# 7_cpu_registers_b.net
KiCad netlist of a schematic drawn in EAGLE
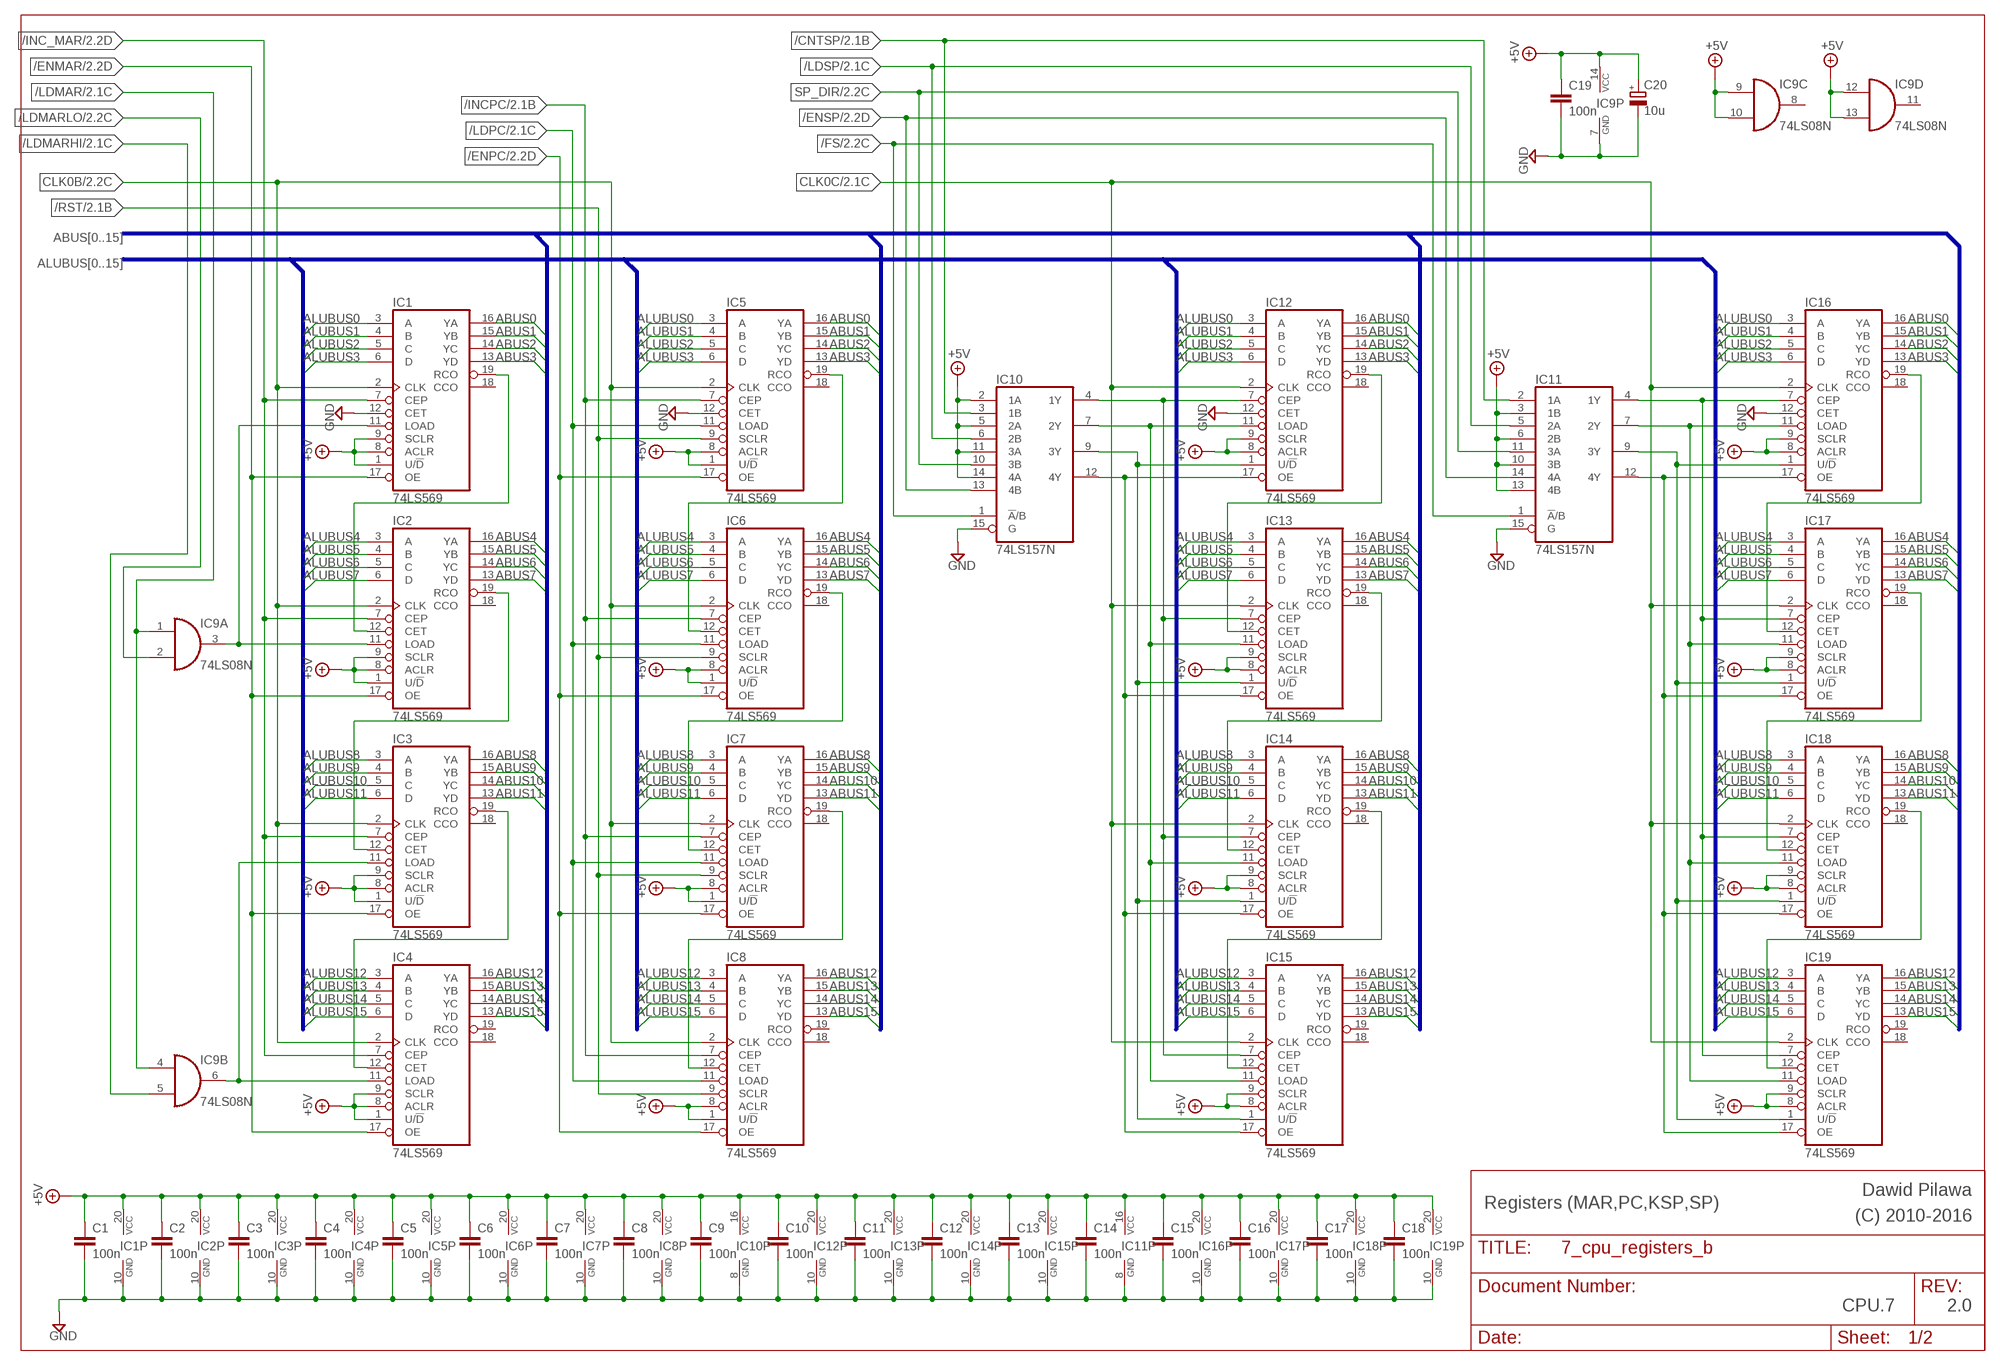
[diagram p0: schematic, sheet 1]
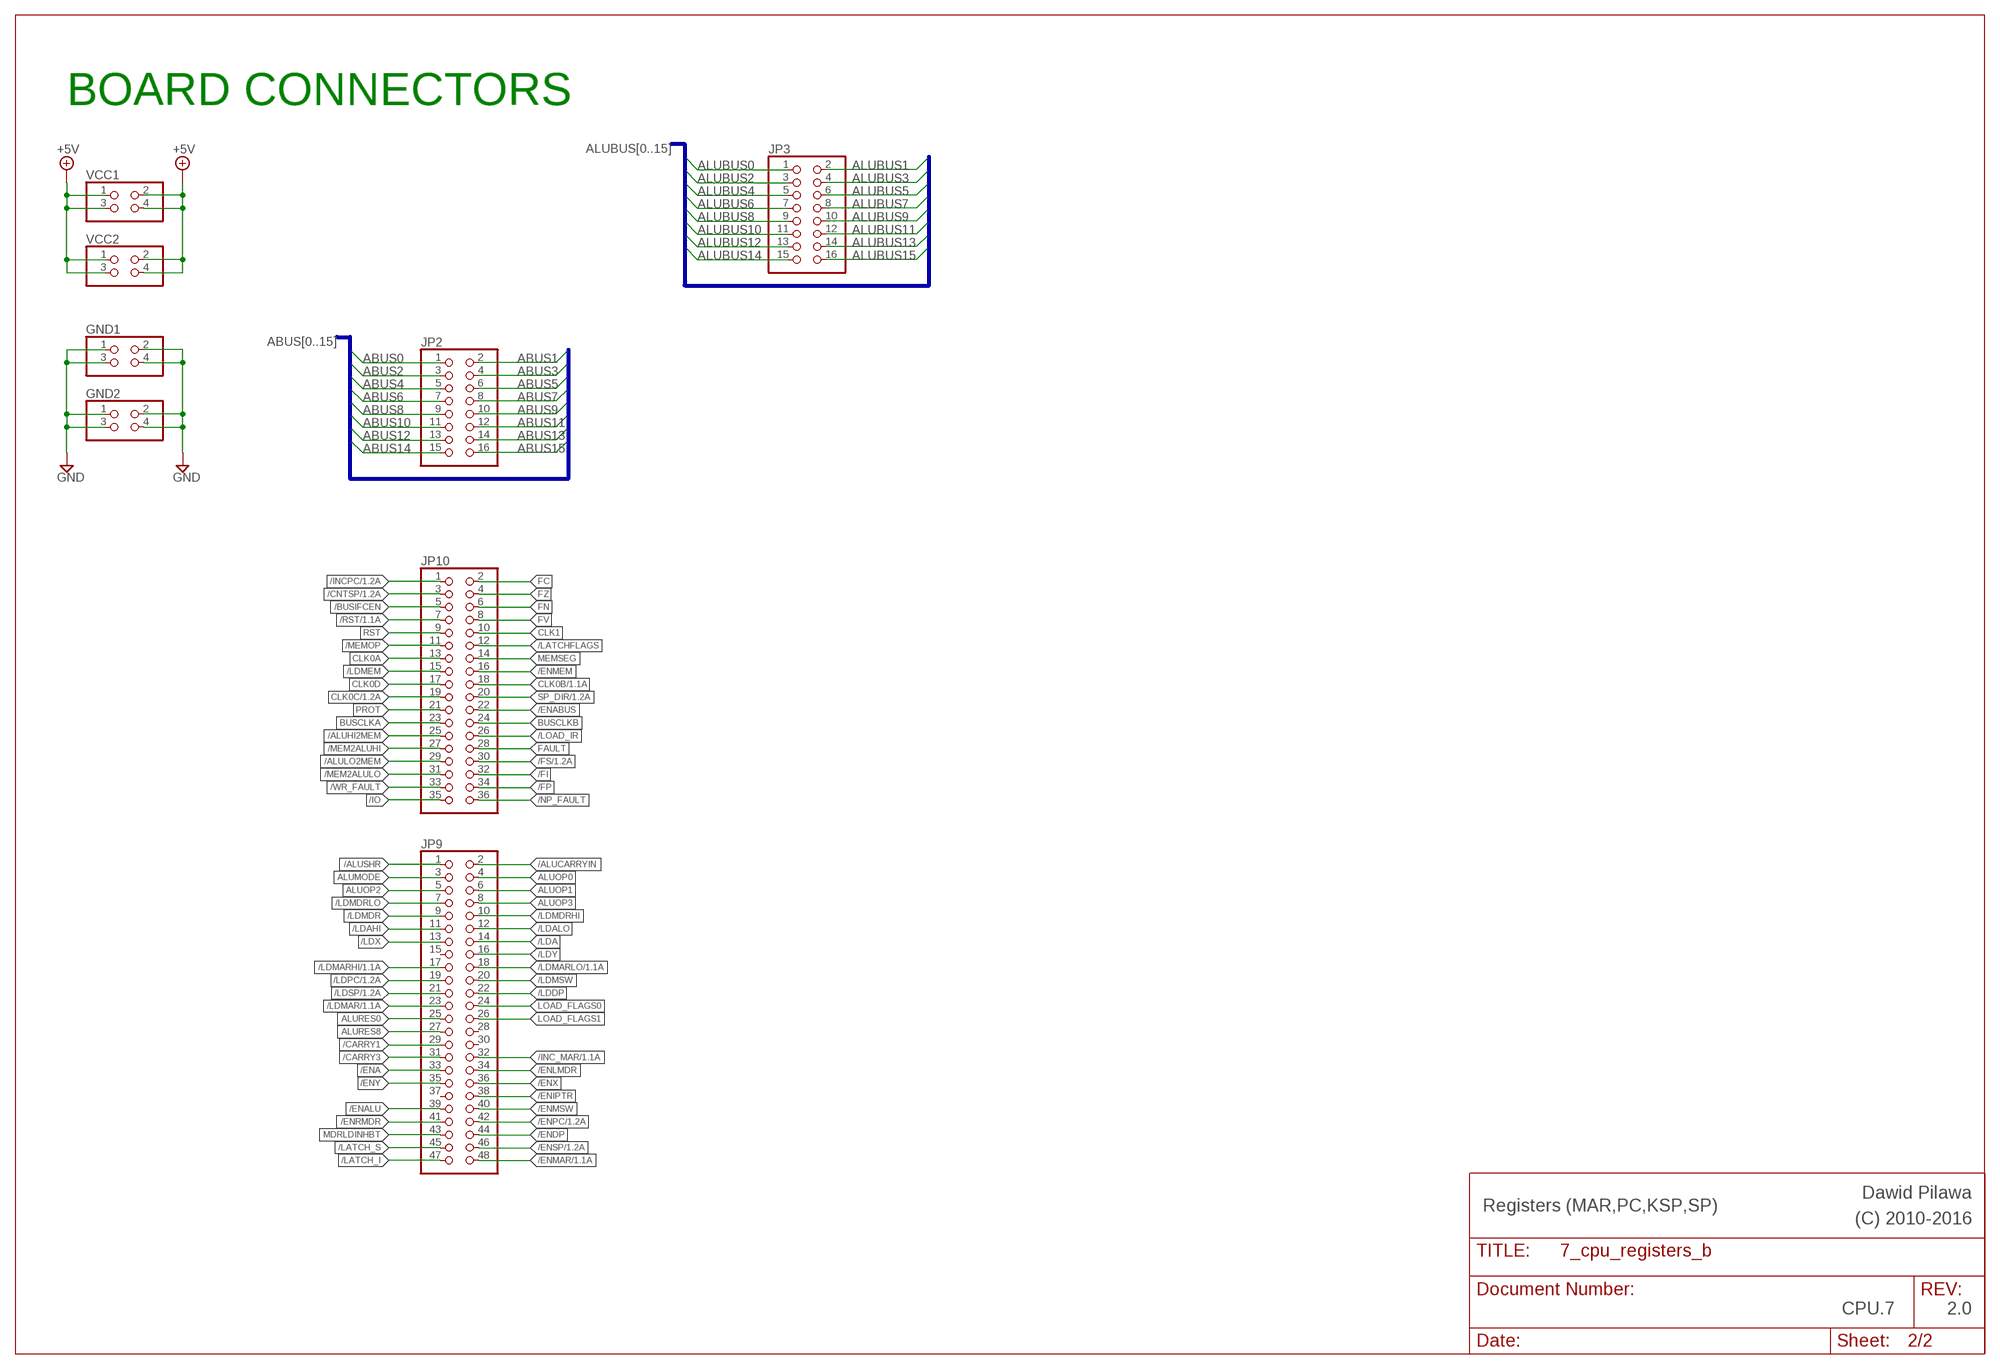
[diagram p1: schematic, sheet 2]

(export (version "E")
  (design (tool "Eeschema 10.0.6"))
  (components
    (comp (ref "C1")
      (value "100n")
      (footprint "eagle-import:C050-024X044")
      (libsource (lib "eagle-import") (part "C-EU050-024X044"))
    )
    (comp (ref "C2")
      (value "100n")
      (footprint "eagle-import:C050-024X044")
      (libsource (lib "eagle-import") (part "C-EU050-024X044"))
    )
    (comp (ref "C3")
      (value "100n")
      (footprint "eagle-import:C050-024X044")
      (libsource (lib "eagle-import") (part "C-EU050-024X044"))
    )
    (comp (ref "C4")
      (value "100n")
      (footprint "eagle-import:C050-024X044")
      (libsource (lib "eagle-import") (part "C-EU050-024X044"))
    )
    (comp (ref "C5")
      (value "100n")
      (footprint "eagle-import:C050-024X044")
      (libsource (lib "eagle-import") (part "C-EU050-024X044"))
    )
    (comp (ref "C6")
      (value "100n")
      (footprint "eagle-import:C050-024X044")
      (libsource (lib "eagle-import") (part "C-EU050-024X044"))
    )
    (comp (ref "C7")
      (value "100n")
      (footprint "eagle-import:C050-024X044")
      (libsource (lib "eagle-import") (part "C-EU050-024X044"))
    )
    (comp (ref "C8")
      (value "100n")
      (footprint "eagle-import:C050-024X044")
      (libsource (lib "eagle-import") (part "C-EU050-024X044"))
    )
    (comp (ref "C9")
      (value "100n")
      (footprint "eagle-import:C050-024X044")
      (libsource (lib "eagle-import") (part "C-EU050-024X044"))
    )
    (comp (ref "C10")
      (value "100n")
      (footprint "eagle-import:C050-024X044")
      (libsource (lib "eagle-import") (part "C-EU050-024X044"))
    )
    (comp (ref "C11")
      (value "100n")
      (footprint "eagle-import:C050-024X044")
      (libsource (lib "eagle-import") (part "C-EU050-024X044"))
    )
    (comp (ref "C12")
      (value "100n")
      (footprint "eagle-import:C050-024X044")
      (libsource (lib "eagle-import") (part "C-EU050-024X044"))
    )
    (comp (ref "C13")
      (value "100n")
      (footprint "eagle-import:C050-024X044")
      (libsource (lib "eagle-import") (part "C-EU050-024X044"))
    )
    (comp (ref "C14")
      (value "100n")
      (footprint "eagle-import:C050-024X044")
      (libsource (lib "eagle-import") (part "C-EU050-024X044"))
    )
    (comp (ref "C15")
      (value "100n")
      (footprint "eagle-import:C050-024X044")
      (libsource (lib "eagle-import") (part "C-EU050-024X044"))
    )
    (comp (ref "C16")
      (value "100n")
      (footprint "eagle-import:C050-024X044")
      (libsource (lib "eagle-import") (part "C-EU050-024X044"))
    )
    (comp (ref "C17")
      (value "100n")
      (footprint "eagle-import:C050-024X044")
      (libsource (lib "eagle-import") (part "C-EU050-024X044"))
    )
    (comp (ref "C18")
      (value "100n")
      (footprint "eagle-import:C050-024X044")
      (libsource (lib "eagle-import") (part "C-EU050-024X044"))
    )
    (comp (ref "C19")
      (value "100n")
      (footprint "eagle-import:C050-024X044")
      (libsource (lib "eagle-import") (part "C-EU050-024X044"))
    )
    (comp (ref "C20")
      (value "10u")
      (footprint "eagle-import:E2,5-6")
      (libsource (lib "eagle-import") (part "CPOL-EUE2.5-6"))
    )
    (comp (ref "IC1")
      (value "74LS569")
      (footprint "eagle-import:DIL20")
      (libsource (lib "eagle-import") (part "74569LS"))
    )
    (comp (ref "IC2")
      (value "74LS569")
      (footprint "eagle-import:DIL20")
      (libsource (lib "eagle-import") (part "74569LS"))
    )
    (comp (ref "IC3")
      (value "74LS569")
      (footprint "eagle-import:DIL20")
      (libsource (lib "eagle-import") (part "74569LS"))
    )
    (comp (ref "IC4")
      (value "74LS569")
      (footprint "eagle-import:DIL20")
      (libsource (lib "eagle-import") (part "74569LS"))
    )
    (comp (ref "IC5")
      (value "74LS569")
      (footprint "eagle-import:DIL20")
      (libsource (lib "eagle-import") (part "74569LS"))
    )
    (comp (ref "IC6")
      (value "74LS569")
      (footprint "eagle-import:DIL20")
      (libsource (lib "eagle-import") (part "74569LS"))
    )
    (comp (ref "IC7")
      (value "74LS569")
      (footprint "eagle-import:DIL20")
      (libsource (lib "eagle-import") (part "74569LS"))
    )
    (comp (ref "IC8")
      (value "74LS569")
      (footprint "eagle-import:DIL20")
      (libsource (lib "eagle-import") (part "74569LS"))
    )
    (comp (ref "IC9")
      (value "74LS08N")
      (footprint "eagle-import:DIL14")
      (libsource (lib "eagle-import") (part "7408NLS"))
    )
    (comp (ref "IC10")
      (value "74LS157N")
      (footprint "eagle-import:DIL16")
      (libsource (lib "eagle-import") (part "74157NLS"))
    )
    (comp (ref "IC11")
      (value "74LS157N")
      (footprint "eagle-import:DIL16")
      (libsource (lib "eagle-import") (part "74157NLS"))
    )
    (comp (ref "IC12")
      (value "74LS569")
      (footprint "eagle-import:DIL20")
      (libsource (lib "eagle-import") (part "74569LS"))
    )
    (comp (ref "IC13")
      (value "74LS569")
      (footprint "eagle-import:DIL20")
      (libsource (lib "eagle-import") (part "74569LS"))
    )
    (comp (ref "IC14")
      (value "74LS569")
      (footprint "eagle-import:DIL20")
      (libsource (lib "eagle-import") (part "74569LS"))
    )
    (comp (ref "IC15")
      (value "74LS569")
      (footprint "eagle-import:DIL20")
      (libsource (lib "eagle-import") (part "74569LS"))
    )
    (comp (ref "IC16")
      (value "74LS569")
      (footprint "eagle-import:DIL20")
      (libsource (lib "eagle-import") (part "74569LS"))
    )
    (comp (ref "IC17")
      (value "74LS569")
      (footprint "eagle-import:DIL20")
      (libsource (lib "eagle-import") (part "74569LS"))
    )
    (comp (ref "IC18")
      (value "74LS569")
      (footprint "eagle-import:DIL20")
      (libsource (lib "eagle-import") (part "74569LS"))
    )
    (comp (ref "IC19")
      (value "74LS569")
      (footprint "eagle-import:DIL20")
      (libsource (lib "eagle-import") (part "74569LS"))
    )
    (comp (ref "GND1")
      (value "PINHD-2X2")
      (footprint "eagle-import:2X02")
      (libsource (lib "eagle-import") (part "PINHD-2X2"))
    )
    (comp (ref "GND2")
      (value "PINHD-2X2")
      (footprint "eagle-import:2X02")
      (libsource (lib "eagle-import") (part "PINHD-2X2"))
    )
    (comp (ref "JP2")
      (value "PINHD-2X8")
      (footprint "eagle-import:2X08")
      (libsource (lib "eagle-import") (part "PINHD-2X8"))
    )
    (comp (ref "JP3")
      (value "PINHD-2X8")
      (footprint "eagle-import:2X08")
      (libsource (lib "eagle-import") (part "PINHD-2X8"))
    )
    (comp (ref "JP9")
      (value "PINHD-2X24")
      (footprint "eagle-import:2X24")
      (libsource (lib "eagle-import") (part "PINHD-2X24"))
    )
    (comp (ref "JP10")
      (value "PINHD-2X18")
      (footprint "eagle-import:2X18")
      (libsource (lib "eagle-import") (part "PINHD-2X18"))
    )
    (comp (ref "VCC1")
      (value "PINHD-2X2")
      (footprint "eagle-import:2X02")
      (libsource (lib "eagle-import") (part "PINHD-2X2"))
    )
    (comp (ref "VCC2")
      (value "PINHD-2X2")
      (footprint "eagle-import:2X02")
      (libsource (lib "eagle-import") (part "PINHD-2X2"))
    )
  )
  (nets
    (net (code "1") (name "+5V") (class "Default")
      (node (ref "C1") (pin "1") (pinfunction "1_1") (pintype "passive"))
      (node (ref "C10") (pin "1") (pinfunction "1_1") (pintype "passive"))
      (node (ref "C11") (pin "1") (pinfunction "1_1") (pintype "passive"))
      (node (ref "C12") (pin "1") (pinfunction "1_1") (pintype "passive"))
      (node (ref "C13") (pin "1") (pinfunction "1_1") (pintype "passive"))
      (node (ref "C14") (pin "1") (pinfunction "1_1") (pintype "passive"))
      (node (ref "C15") (pin "1") (pinfunction "1_1") (pintype "passive"))
      (node (ref "C16") (pin "1") (pinfunction "1_1") (pintype "passive"))
      (node (ref "C17") (pin "1") (pinfunction "1_1") (pintype "passive"))
      (node (ref "C18") (pin "1") (pinfunction "1_1") (pintype "passive"))
      (node (ref "C19") (pin "1") (pinfunction "1_1") (pintype "passive"))
      (node (ref "C2") (pin "1") (pinfunction "1_1") (pintype "passive"))
      (node (ref "C20") (pin "+") (pinfunction "+_+") (pintype "passive"))
      (node (ref "C3") (pin "1") (pinfunction "1_1") (pintype "passive"))
      (node (ref "C4") (pin "1") (pinfunction "1_1") (pintype "passive"))
      (node (ref "C5") (pin "1") (pinfunction "1_1") (pintype "passive"))
      (node (ref "C6") (pin "1") (pinfunction "1_1") (pintype "passive"))
      (node (ref "C7") (pin "1") (pinfunction "1_1") (pintype "passive"))
      (node (ref "C8") (pin "1") (pinfunction "1_1") (pintype "passive"))
      (node (ref "C9") (pin "1") (pinfunction "1_1") (pintype "passive"))
      (node (ref "IC1") (pin "1") (pinfunction "U/~{D}_1") (pintype "input"))
      (node (ref "IC1") (pin "20") (pinfunction "VCC_20") (pintype "power_in"))
      (node (ref "IC1") (pin "8") (pinfunction "ACLR_8") (pintype "input"))
      (node (ref "IC1") (pin "9") (pinfunction "SCLR_9") (pintype "input"))
      (node (ref "IC10") (pin "11") (pinfunction "3A_11") (pintype "input"))
      (node (ref "IC10") (pin "14") (pinfunction "4A_14") (pintype "input"))
      (node (ref "IC10") (pin "16") (pinfunction "VCC_16") (pintype "power_in"))
      (node (ref "IC10") (pin "2") (pinfunction "1A_2") (pintype "input"))
      (node (ref "IC10") (pin "5") (pinfunction "2A_5") (pintype "input"))
      (node (ref "IC11") (pin "10") (pinfunction "3B_10") (pintype "input"))
      (node (ref "IC11") (pin "13") (pinfunction "4B_13") (pintype "input"))
      (node (ref "IC11") (pin "16") (pinfunction "VCC_16") (pintype "power_in"))
      (node (ref "IC11") (pin "3") (pinfunction "1B_3") (pintype "input"))
      (node (ref "IC11") (pin "6") (pinfunction "2B_6") (pintype "input"))
      (node (ref "IC12") (pin "20") (pinfunction "VCC_20") (pintype "power_in"))
      (node (ref "IC12") (pin "8") (pinfunction "ACLR_8") (pintype "input"))
      (node (ref "IC12") (pin "9") (pinfunction "SCLR_9") (pintype "input"))
      (node (ref "IC13") (pin "20") (pinfunction "VCC_20") (pintype "power_in"))
      (node (ref "IC13") (pin "8") (pinfunction "ACLR_8") (pintype "input"))
      (node (ref "IC13") (pin "9") (pinfunction "SCLR_9") (pintype "input"))
      (node (ref "IC14") (pin "20") (pinfunction "VCC_20") (pintype "power_in"))
      (node (ref "IC14") (pin "8") (pinfunction "ACLR_8") (pintype "input"))
      (node (ref "IC14") (pin "9") (pinfunction "SCLR_9") (pintype "input"))
      (node (ref "IC15") (pin "20") (pinfunction "VCC_20") (pintype "power_in"))
      (node (ref "IC15") (pin "8") (pinfunction "ACLR_8") (pintype "input"))
      (node (ref "IC15") (pin "9") (pinfunction "SCLR_9") (pintype "input"))
      (node (ref "IC16") (pin "20") (pinfunction "VCC_20") (pintype "power_in"))
      (node (ref "IC16") (pin "8") (pinfunction "ACLR_8") (pintype "input"))
      (node (ref "IC16") (pin "9") (pinfunction "SCLR_9") (pintype "input"))
      (node (ref "IC17") (pin "20") (pinfunction "VCC_20") (pintype "power_in"))
      (node (ref "IC17") (pin "8") (pinfunction "ACLR_8") (pintype "input"))
      (node (ref "IC17") (pin "9") (pinfunction "SCLR_9") (pintype "input"))
      (node (ref "IC18") (pin "20") (pinfunction "VCC_20") (pintype "power_in"))
      (node (ref "IC18") (pin "8") (pinfunction "ACLR_8") (pintype "input"))
      (node (ref "IC18") (pin "9") (pinfunction "SCLR_9") (pintype "input"))
      (node (ref "IC19") (pin "20") (pinfunction "VCC_20") (pintype "power_in"))
      (node (ref "IC19") (pin "8") (pinfunction "ACLR_8") (pintype "input"))
      (node (ref "IC19") (pin "9") (pinfunction "SCLR_9") (pintype "input"))
      (node (ref "IC2") (pin "1") (pinfunction "U/~{D}_1") (pintype "input"))
      (node (ref "IC2") (pin "20") (pinfunction "VCC_20") (pintype "power_in"))
      (node (ref "IC2") (pin "8") (pinfunction "ACLR_8") (pintype "input"))
      (node (ref "IC2") (pin "9") (pinfunction "SCLR_9") (pintype "input"))
      (node (ref "IC3") (pin "1") (pinfunction "U/~{D}_1") (pintype "input"))
      (node (ref "IC3") (pin "20") (pinfunction "VCC_20") (pintype "power_in"))
      (node (ref "IC3") (pin "8") (pinfunction "ACLR_8") (pintype "input"))
      (node (ref "IC3") (pin "9") (pinfunction "SCLR_9") (pintype "input"))
      (node (ref "IC4") (pin "1") (pinfunction "U/~{D}_1") (pintype "input"))
      (node (ref "IC4") (pin "20") (pinfunction "VCC_20") (pintype "power_in"))
      (node (ref "IC4") (pin "8") (pinfunction "ACLR_8") (pintype "input"))
      (node (ref "IC4") (pin "9") (pinfunction "SCLR_9") (pintype "input"))
      (node (ref "IC5") (pin "1") (pinfunction "U/~{D}_1") (pintype "input"))
      (node (ref "IC5") (pin "20") (pinfunction "VCC_20") (pintype "power_in"))
      (node (ref "IC5") (pin "8") (pinfunction "ACLR_8") (pintype "input"))
      (node (ref "IC6") (pin "1") (pinfunction "U/~{D}_1") (pintype "input"))
      (node (ref "IC6") (pin "20") (pinfunction "VCC_20") (pintype "power_in"))
      (node (ref "IC6") (pin "8") (pinfunction "ACLR_8") (pintype "input"))
      (node (ref "IC7") (pin "1") (pinfunction "U/~{D}_1") (pintype "input"))
      (node (ref "IC7") (pin "20") (pinfunction "VCC_20") (pintype "power_in"))
      (node (ref "IC7") (pin "8") (pinfunction "ACLR_8") (pintype "input"))
      (node (ref "IC8") (pin "1") (pinfunction "U/~{D}_1") (pintype "input"))
      (node (ref "IC8") (pin "20") (pinfunction "VCC_20") (pintype "power_in"))
      (node (ref "IC8") (pin "8") (pinfunction "ACLR_8") (pintype "input"))
      (node (ref "IC9") (pin "10") (pinfunction "I1_10") (pintype "input"))
      (node (ref "IC9") (pin "12") (pinfunction "I0_12") (pintype "input"))
      (node (ref "IC9") (pin "13") (pinfunction "I1_13") (pintype "input"))
      (node (ref "IC9") (pin "14") (pinfunction "VCC_14") (pintype "power_in"))
      (node (ref "IC9") (pin "9") (pinfunction "I0_9") (pintype "input"))
      (node (ref "VCC1") (pin "1") (pinfunction "1_1") (pintype "passive"))
      (node (ref "VCC1") (pin "2") (pinfunction "2_2") (pintype "passive"))
      (node (ref "VCC1") (pin "3") (pinfunction "3_3") (pintype "passive"))
      (node (ref "VCC1") (pin "4") (pinfunction "4_4") (pintype "passive"))
      (node (ref "VCC2") (pin "1") (pinfunction "1_1") (pintype "passive"))
      (node (ref "VCC2") (pin "2") (pinfunction "2_2") (pintype "passive"))
      (node (ref "VCC2") (pin "3") (pinfunction "3_3") (pintype "passive"))
      (node (ref "VCC2") (pin "4") (pinfunction "4_4") (pintype "passive"))
    )
    (net (code "6") (name "ABUS0") (class "Default")
      (node (ref "IC1") (pin "16") (pinfunction "YA_16") (pintype "open_collector"))
      (node (ref "IC12") (pin "16") (pinfunction "YA_16") (pintype "open_collector"))
      (node (ref "IC16") (pin "16") (pinfunction "YA_16") (pintype "open_collector"))
      (node (ref "IC5") (pin "16") (pinfunction "YA_16") (pintype "open_collector"))
      (node (ref "JP2") (pin "1") (pinfunction "1_1") (pintype "passive"))
    )
    (net (code "7") (name "ABUS1") (class "Default")
      (node (ref "IC1") (pin "15") (pinfunction "YB_15") (pintype "open_collector"))
      (node (ref "IC12") (pin "15") (pinfunction "YB_15") (pintype "open_collector"))
      (node (ref "IC16") (pin "15") (pinfunction "YB_15") (pintype "open_collector"))
      (node (ref "IC5") (pin "15") (pinfunction "YB_15") (pintype "open_collector"))
      (node (ref "JP2") (pin "2") (pinfunction "2_2") (pintype "passive"))
    )
    (net (code "8") (name "ABUS2") (class "Default")
      (node (ref "IC1") (pin "14") (pinfunction "YC_14") (pintype "open_collector"))
      (node (ref "IC12") (pin "14") (pinfunction "YC_14") (pintype "open_collector"))
      (node (ref "IC16") (pin "14") (pinfunction "YC_14") (pintype "open_collector"))
      (node (ref "IC5") (pin "14") (pinfunction "YC_14") (pintype "open_collector"))
      (node (ref "JP2") (pin "3") (pinfunction "3_3") (pintype "passive"))
    )
    (net (code "9") (name "ABUS3") (class "Default")
      (node (ref "IC1") (pin "13") (pinfunction "YD_13") (pintype "open_collector"))
      (node (ref "IC12") (pin "13") (pinfunction "YD_13") (pintype "open_collector"))
      (node (ref "IC16") (pin "13") (pinfunction "YD_13") (pintype "open_collector"))
      (node (ref "IC5") (pin "13") (pinfunction "YD_13") (pintype "open_collector"))
      (node (ref "JP2") (pin "4") (pinfunction "4_4") (pintype "passive"))
    )
    (net (code "10") (name "ABUS4") (class "Default")
      (node (ref "IC13") (pin "16") (pinfunction "YA_16") (pintype "open_collector"))
      (node (ref "IC17") (pin "16") (pinfunction "YA_16") (pintype "open_collector"))
      (node (ref "IC2") (pin "16") (pinfunction "YA_16") (pintype "open_collector"))
      (node (ref "IC6") (pin "16") (pinfunction "YA_16") (pintype "open_collector"))
      (node (ref "JP2") (pin "5") (pinfunction "5_5") (pintype "passive"))
    )
    (net (code "11") (name "ABUS5") (class "Default")
      (node (ref "IC13") (pin "15") (pinfunction "YB_15") (pintype "open_collector"))
      (node (ref "IC17") (pin "15") (pinfunction "YB_15") (pintype "open_collector"))
      (node (ref "IC2") (pin "15") (pinfunction "YB_15") (pintype "open_collector"))
      (node (ref "IC6") (pin "15") (pinfunction "YB_15") (pintype "open_collector"))
      (node (ref "JP2") (pin "6") (pinfunction "6_6") (pintype "passive"))
    )
    (net (code "12") (name "ABUS6") (class "Default")
      (node (ref "IC13") (pin "14") (pinfunction "YC_14") (pintype "open_collector"))
      (node (ref "IC17") (pin "14") (pinfunction "YC_14") (pintype "open_collector"))
      (node (ref "IC2") (pin "14") (pinfunction "YC_14") (pintype "open_collector"))
      (node (ref "IC6") (pin "14") (pinfunction "YC_14") (pintype "open_collector"))
      (node (ref "JP2") (pin "7") (pinfunction "7_7") (pintype "passive"))
    )
    (net (code "13") (name "ABUS7") (class "Default")
      (node (ref "IC13") (pin "13") (pinfunction "YD_13") (pintype "open_collector"))
      (node (ref "IC17") (pin "13") (pinfunction "YD_13") (pintype "open_collector"))
      (node (ref "IC2") (pin "13") (pinfunction "YD_13") (pintype "open_collector"))
      (node (ref "IC6") (pin "13") (pinfunction "YD_13") (pintype "open_collector"))
      (node (ref "JP2") (pin "8") (pinfunction "8_8") (pintype "passive"))
    )
    (net (code "14") (name "ABUS8") (class "Default")
      (node (ref "IC14") (pin "16") (pinfunction "YA_16") (pintype "open_collector"))
      (node (ref "IC18") (pin "16") (pinfunction "YA_16") (pintype "open_collector"))
      (node (ref "IC3") (pin "16") (pinfunction "YA_16") (pintype "open_collector"))
      (node (ref "IC7") (pin "16") (pinfunction "YA_16") (pintype "open_collector"))
      (node (ref "JP2") (pin "9") (pinfunction "9_9") (pintype "passive"))
    )
    (net (code "15") (name "ABUS9") (class "Default")
      (node (ref "IC14") (pin "15") (pinfunction "YB_15") (pintype "open_collector"))
      (node (ref "IC18") (pin "15") (pinfunction "YB_15") (pintype "open_collector"))
      (node (ref "IC3") (pin "15") (pinfunction "YB_15") (pintype "open_collector"))
      (node (ref "IC7") (pin "15") (pinfunction "YB_15") (pintype "open_collector"))
      (node (ref "JP2") (pin "10") (pinfunction "10_10") (pintype "passive"))
    )
    (net (code "16") (name "ABUS10") (class "Default")
      (node (ref "IC14") (pin "14") (pinfunction "YC_14") (pintype "open_collector"))
      (node (ref "IC18") (pin "14") (pinfunction "YC_14") (pintype "open_collector"))
      (node (ref "IC3") (pin "14") (pinfunction "YC_14") (pintype "open_collector"))
      (node (ref "IC7") (pin "14") (pinfunction "YC_14") (pintype "open_collector"))
      (node (ref "JP2") (pin "11") (pinfunction "11_11") (pintype "passive"))
    )
    (net (code "17") (name "ABUS11") (class "Default")
      (node (ref "IC14") (pin "13") (pinfunction "YD_13") (pintype "open_collector"))
      (node (ref "IC18") (pin "13") (pinfunction "YD_13") (pintype "open_collector"))
      (node (ref "IC3") (pin "13") (pinfunction "YD_13") (pintype "open_collector"))
      (node (ref "IC7") (pin "13") (pinfunction "YD_13") (pintype "open_collector"))
      (node (ref "JP2") (pin "12") (pinfunction "12_12") (pintype "passive"))
    )
    (net (code "18") (name "ABUS12") (class "Default")
      (node (ref "IC15") (pin "16") (pinfunction "YA_16") (pintype "open_collector"))
      (node (ref "IC19") (pin "16") (pinfunction "YA_16") (pintype "open_collector"))
      (node (ref "IC4") (pin "16") (pinfunction "YA_16") (pintype "open_collector"))
      (node (ref "IC8") (pin "16") (pinfunction "YA_16") (pintype "open_collector"))
      (node (ref "JP2") (pin "13") (pinfunction "13_13") (pintype "passive"))
    )
    (net (code "19") (name "ABUS13") (class "Default")
      (node (ref "IC15") (pin "15") (pinfunction "YB_15") (pintype "open_collector"))
      (node (ref "IC19") (pin "15") (pinfunction "YB_15") (pintype "open_collector"))
      (node (ref "IC4") (pin "15") (pinfunction "YB_15") (pintype "open_collector"))
      (node (ref "IC8") (pin "15") (pinfunction "YB_15") (pintype "open_collector"))
      (node (ref "JP2") (pin "14") (pinfunction "14_14") (pintype "passive"))
    )
    (net (code "20") (name "ABUS14") (class "Default")
      (node (ref "IC15") (pin "14") (pinfunction "YC_14") (pintype "open_collector"))
      (node (ref "IC19") (pin "14") (pinfunction "YC_14") (pintype "open_collector"))
      (node (ref "IC4") (pin "14") (pinfunction "YC_14") (pintype "open_collector"))
      (node (ref "IC8") (pin "14") (pinfunction "YC_14") (pintype "open_collector"))
      (node (ref "JP2") (pin "15") (pinfunction "15_15") (pintype "passive"))
    )
    (net (code "21") (name "ABUS15") (class "Default")
      (node (ref "IC15") (pin "13") (pinfunction "YD_13") (pintype "open_collector"))
      (node (ref "IC19") (pin "13") (pinfunction "YD_13") (pintype "open_collector"))
      (node (ref "IC4") (pin "13") (pinfunction "YD_13") (pintype "open_collector"))
      (node (ref "IC8") (pin "13") (pinfunction "YD_13") (pintype "open_collector"))
      (node (ref "JP2") (pin "16") (pinfunction "16_16") (pintype "passive"))
    )
    (net (code "22") (name "ALUBUS0") (class "Default")
      (node (ref "IC1") (pin "3") (pinfunction "A_3") (pintype "input"))
      (node (ref "IC12") (pin "3") (pinfunction "A_3") (pintype "input"))
      (node (ref "IC16") (pin "3") (pinfunction "A_3") (pintype "input"))
      (node (ref "IC5") (pin "3") (pinfunction "A_3") (pintype "input"))
      (node (ref "JP3") (pin "1") (pinfunction "1_1") (pintype "passive"))
    )
    (net (code "23") (name "ALUBUS1") (class "Default")
      (node (ref "IC1") (pin "4") (pinfunction "B_4") (pintype "input"))
      (node (ref "IC12") (pin "4") (pinfunction "B_4") (pintype "input"))
      (node (ref "IC16") (pin "4") (pinfunction "B_4") (pintype "input"))
      (node (ref "IC5") (pin "4") (pinfunction "B_4") (pintype "input"))
      (node (ref "JP3") (pin "2") (pinfunction "2_2") (pintype "passive"))
    )
    (net (code "24") (name "ALUBUS2") (class "Default")
      (node (ref "IC1") (pin "5") (pinfunction "C_5") (pintype "input"))
      (node (ref "IC12") (pin "5") (pinfunction "C_5") (pintype "input"))
      (node (ref "IC16") (pin "5") (pinfunction "C_5") (pintype "input"))
      (node (ref "IC5") (pin "5") (pinfunction "C_5") (pintype "input"))
      (node (ref "JP3") (pin "3") (pinfunction "3_3") (pintype "passive"))
    )
    (net (code "25") (name "ALUBUS3") (class "Default")
      (node (ref "IC1") (pin "6") (pinfunction "D_6") (pintype "input"))
      (node (ref "IC12") (pin "6") (pinfunction "D_6") (pintype "input"))
      (node (ref "IC16") (pin "6") (pinfunction "D_6") (pintype "input"))
      (node (ref "IC5") (pin "6") (pinfunction "D_6") (pintype "input"))
      (node (ref "JP3") (pin "4") (pinfunction "4_4") (pintype "passive"))
    )
    (net (code "26") (name "ALUBUS4") (class "Default")
      (node (ref "IC13") (pin "3") (pinfunction "A_3") (pintype "input"))
      (node (ref "IC17") (pin "3") (pinfunction "A_3") (pintype "input"))
      (node (ref "IC2") (pin "3") (pinfunction "A_3") (pintype "input"))
      (node (ref "IC6") (pin "3") (pinfunction "A_3") (pintype "input"))
      (node (ref "JP3") (pin "5") (pinfunction "5_5") (pintype "passive"))
    )
    (net (code "27") (name "ALUBUS5") (class "Default")
      (node (ref "IC13") (pin "4") (pinfunction "B_4") (pintype "input"))
      (node (ref "IC17") (pin "4") (pinfunction "B_4") (pintype "input"))
      (node (ref "IC2") (pin "4") (pinfunction "B_4") (pintype "input"))
      (node (ref "IC6") (pin "4") (pinfunction "B_4") (pintype "input"))
      (node (ref "JP3") (pin "6") (pinfunction "6_6") (pintype "passive"))
    )
    (net (code "28") (name "ALUBUS6") (class "Default")
      (node (ref "IC13") (pin "5") (pinfunction "C_5") (pintype "input"))
      (node (ref "IC17") (pin "5") (pinfunction "C_5") (pintype "input"))
      (node (ref "IC2") (pin "5") (pinfunction "C_5") (pintype "input"))
      (node (ref "IC6") (pin "5") (pinfunction "C_5") (pintype "input"))
      (node (ref "JP3") (pin "7") (pinfunction "7_7") (pintype "passive"))
    )
    (net (code "29") (name "ALUBUS7") (class "Default")
      (node (ref "IC13") (pin "6") (pinfunction "D_6") (pintype "input"))
      (node (ref "IC17") (pin "6") (pinfunction "D_6") (pintype "input"))
      (node (ref "IC2") (pin "6") (pinfunction "D_6") (pintype "input"))
      (node (ref "IC6") (pin "6") (pinfunction "D_6") (pintype "input"))
      (node (ref "JP3") (pin "8") (pinfunction "8_8") (pintype "passive"))
    )
    (net (code "30") (name "ALUBUS8") (class "Default")
      (node (ref "IC14") (pin "3") (pinfunction "A_3") (pintype "input"))
      (node (ref "IC18") (pin "3") (pinfunction "A_3") (pintype "input"))
      (node (ref "IC3") (pin "3") (pinfunction "A_3") (pintype "input"))
      (node (ref "IC7") (pin "3") (pinfunction "A_3") (pintype "input"))
      (node (ref "JP3") (pin "9") (pinfunction "9_9") (pintype "passive"))
    )
    (net (code "31") (name "ALUBUS9") (class "Default")
      (node (ref "IC14") (pin "4") (pinfunction "B_4") (pintype "input"))
      (node (ref "IC18") (pin "4") (pinfunction "B_4") (pintype "input"))
      (node (ref "IC3") (pin "4") (pinfunction "B_4") (pintype "input"))
      (node (ref "IC7") (pin "4") (pinfunction "B_4") (pintype "input"))
      (node (ref "JP3") (pin "10") (pinfunction "10_10") (pintype "passive"))
    )
    (net (code "32") (name "ALUBUS10") (class "Default")
      (node (ref "IC14") (pin "5") (pinfunction "C_5") (pintype "input"))
      (node (ref "IC18") (pin "5") (pinfunction "C_5") (pintype "input"))
      (node (ref "IC3") (pin "5") (pinfunction "C_5") (pintype "input"))
      (node (ref "IC7") (pin "5") (pinfunction "C_5") (pintype "input"))
      (node (ref "JP3") (pin "11") (pinfunction "11_11") (pintype "passive"))
    )
    (net (code "33") (name "ALUBUS11") (class "Default")
      (node (ref "IC14") (pin "6") (pinfunction "D_6") (pintype "input"))
      (node (ref "IC18") (pin "6") (pinfunction "D_6") (pintype "input"))
      (node (ref "IC3") (pin "6") (pinfunction "D_6") (pintype "input"))
      (node (ref "IC7") (pin "6") (pinfunction "D_6") (pintype "input"))
      (node (ref "JP3") (pin "12") (pinfunction "12_12") (pintype "passive"))
    )
    (net (code "34") (name "ALUBUS12") (class "Default")
      (node (ref "IC15") (pin "3") (pinfunction "A_3") (pintype "input"))
      (node (ref "IC19") (pin "3") (pinfunction "A_3") (pintype "input"))
      (node (ref "IC4") (pin "3") (pinfunction "A_3") (pintype "input"))
      (node (ref "IC8") (pin "3") (pinfunction "A_3") (pintype "input"))
      (node (ref "JP3") (pin "13") (pinfunction "13_13") (pintype "passive"))
    )
    (net (code "35") (name "ALUBUS13") (class "Default")
      (node (ref "IC15") (pin "4") (pinfunction "B_4") (pintype "input"))
      (node (ref "IC19") (pin "4") (pinfunction "B_4") (pintype "input"))
      (node (ref "IC4") (pin "4") (pinfunction "B_4") (pintype "input"))
      (node (ref "IC8") (pin "4") (pinfunction "B_4") (pintype "input"))
      (node (ref "JP3") (pin "14") (pinfunction "14_14") (pintype "passive"))
    )
    (net (code "36") (name "ALUBUS14") (class "Default")
      (node (ref "IC15") (pin "5") (pinfunction "C_5") (pintype "input"))
      (node (ref "IC19") (pin "5") (pinfunction "C_5") (pintype "input"))
      (node (ref "IC4") (pin "5") (pinfunction "C_5") (pintype "input"))
      (node (ref "IC8") (pin "5") (pinfunction "C_5") (pintype "input"))
      (node (ref "JP3") (pin "15") (pinfunction "15_15") (pintype "passive"))
    )
    (net (code "37") (name "ALUBUS15") (class "Default")
      (node (ref "IC15") (pin "6") (pinfunction "D_6") (pintype "input"))
      (node (ref "IC19") (pin "6") (pinfunction "D_6") (pintype "input"))
      (node (ref "IC4") (pin "6") (pinfunction "D_6") (pintype "input"))
      (node (ref "IC8") (pin "6") (pinfunction "D_6") (pintype "input"))
      (node (ref "JP3") (pin "16") (pinfunction "16_16") (pintype "passive"))
    )
    (net (code "38") (name "ALUMODE") (class "Default")
      (node (ref "JP9") (pin "3") (pinfunction "3_3") (pintype "passive"))
    )
    (net (code "39") (name "ALUOP0") (class "Default")
      (node (ref "JP9") (pin "4") (pinfunction "4_4") (pintype "passive"))
    )
    (net (code "40") (name "ALUOP1") (class "Default")
      (node (ref "JP9") (pin "6") (pinfunction "6_6") (pintype "passive"))
    )
    (net (code "41") (name "ALUOP2") (class "Default")
      (node (ref "JP9") (pin "5") (pinfunction "5_5") (pintype "passive"))
    )
    (net (code "42") (name "ALUOP3") (class "Default")
      (node (ref "JP9") (pin "8") (pinfunction "8_8") (pintype "passive"))
    )
    (net (code "43") (name "ALURES0") (class "Default")
      (node (ref "JP9") (pin "25") (pinfunction "25_25") (pintype "passive"))
    )
    (net (code "44") (name "ALURES8") (class "Default")
      (node (ref "JP9") (pin "27") (pinfunction "27_27") (pintype "passive"))
    )
    (net (code "45") (name "BUSCLKA") (class "Default")
      (node (ref "JP10") (pin "23") (pinfunction "23_23") (pintype "passive"))
    )
    (net (code "46") (name "BUSCLKB") (class "Default")
      (node (ref "JP10") (pin "24") (pinfunction "24_24") (pintype "passive"))
    )
    (net (code "47") (name "CLK0A") (class "Default")
      (node (ref "JP10") (pin "13") (pinfunction "13_13") (pintype "passive"))
    )
    (net (code "48") (name "CLK0B") (class "Default")
      (node (ref "IC1") (pin "2") (pinfunction "CLK_2") (pintype "input"))
      (node (ref "IC2") (pin "2") (pinfunction "CLK_2") (pintype "input"))
      (node (ref "IC3") (pin "2") (pinfunction "CLK_2") (pintype "input"))
      (node (ref "IC4") (pin "2") (pinfunction "CLK_2") (pintype "input"))
      (node (ref "IC5") (pin "2") (pinfunction "CLK_2") (pintype "input"))
      (node (ref "IC6") (pin "2") (pinfunction "CLK_2") (pintype "input"))
      (node (ref "IC7") (pin "2") (pinfunction "CLK_2") (pintype "input"))
      (node (ref "IC8") (pin "2") (pinfunction "CLK_2") (pintype "input"))
      (node (ref "JP10") (pin "18") (pinfunction "18_18") (pintype "passive"))
    )
    (net (code "49") (name "CLK0C") (class "Default")
      (node (ref "IC12") (pin "2") (pinfunction "CLK_2") (pintype "input"))
      (node (ref "IC13") (pin "2") (pinfunction "CLK_2") (pintype "input"))
      (node (ref "IC14") (pin "2") (pinfunction "CLK_2") (pintype "input"))
      (node (ref "IC15") (pin "2") (pinfunction "CLK_2") (pintype "input"))
      (node (ref "IC16") (pin "2") (pinfunction "CLK_2") (pintype "input"))
      (node (ref "IC17") (pin "2") (pinfunction "CLK_2") (pintype "input"))
      (node (ref "IC18") (pin "2") (pinfunction "CLK_2") (pintype "input"))
      (node (ref "IC19") (pin "2") (pinfunction "CLK_2") (pintype "input"))
      (node (ref "JP10") (pin "19") (pinfunction "19_19") (pintype "passive"))
    )
    (net (code "50") (name "CLK0D") (class "Default")
      (node (ref "JP10") (pin "17") (pinfunction "17_17") (pintype "passive"))
    )
    (net (code "51") (name "CLK1") (class "Default")
      (node (ref "JP10") (pin "10") (pinfunction "10_10") (pintype "passive"))
    )
    (net (code "52") (name "FAULT") (class "Default")
      (node (ref "JP10") (pin "28") (pinfunction "28_28") (pintype "passive"))
    )
    (net (code "53") (name "FC") (class "Default")
      (node (ref "JP10") (pin "2") (pinfunction "2_2") (pintype "passive"))
    )
    (net (code "54") (name "FN") (class "Default")
      (node (ref "JP10") (pin "6") (pinfunction "6_6") (pintype "passive"))
    )
    (net (code "55") (name "FV") (class "Default")
      (node (ref "JP10") (pin "8") (pinfunction "8_8") (pintype "passive"))
    )
    (net (code "56") (name "FZ") (class "Default")
      (node (ref "JP10") (pin "4") (pinfunction "4_4") (pintype "passive"))
    )
    (net (code "57") (name "GND") (class "Default")
      (node (ref "C1") (pin "2") (pinfunction "2_2") (pintype "passive"))
      (node (ref "C10") (pin "2") (pinfunction "2_2") (pintype "passive"))
      (node (ref "C11") (pin "2") (pinfunction "2_2") (pintype "passive"))
      (node (ref "C12") (pin "2") (pinfunction "2_2") (pintype "passive"))
      (node (ref "C13") (pin "2") (pinfunction "2_2") (pintype "passive"))
      (node (ref "C14") (pin "2") (pinfunction "2_2") (pintype "passive"))
      (node (ref "C15") (pin "2") (pinfunction "2_2") (pintype "passive"))
      (node (ref "C16") (pin "2") (pinfunction "2_2") (pintype "passive"))
      (node (ref "C17") (pin "2") (pinfunction "2_2") (pintype "passive"))
      (node (ref "C18") (pin "2") (pinfunction "2_2") (pintype "passive"))
      (node (ref "C19") (pin "2") (pinfunction "2_2") (pintype "passive"))
      (node (ref "C2") (pin "2") (pinfunction "2_2") (pintype "passive"))
      (node (ref "C20") (pin "-") (pinfunction "-_-") (pintype "passive"))
      (node (ref "C3") (pin "2") (pinfunction "2_2") (pintype "passive"))
      (node (ref "C4") (pin "2") (pinfunction "2_2") (pintype "passive"))
      (node (ref "C5") (pin "2") (pinfunction "2_2") (pintype "passive"))
      (node (ref "C6") (pin "2") (pinfunction "2_2") (pintype "passive"))
      (node (ref "C7") (pin "2") (pinfunction "2_2") (pintype "passive"))
      (node (ref "C8") (pin "2") (pinfunction "2_2") (pintype "passive"))
      (node (ref "C9") (pin "2") (pinfunction "2_2") (pintype "passive"))
      (node (ref "GND1") (pin "1") (pinfunction "1_1") (pintype "passive"))
      (node (ref "GND1") (pin "2") (pinfunction "2_2") (pintype "passive"))
      (node (ref "GND1") (pin "3") (pinfunction "3_3") (pintype "passive"))
      (node (ref "GND1") (pin "4") (pinfunction "4_4") (pintype "passive"))
      (node (ref "GND2") (pin "1") (pinfunction "1_1") (pintype "passive"))
      (node (ref "GND2") (pin "2") (pinfunction "2_2") (pintype "passive"))
      (node (ref "GND2") (pin "3") (pinfunction "3_3") (pintype "passive"))
      (node (ref "GND2") (pin "4") (pinfunction "4_4") (pintype "passive"))
      (node (ref "IC1") (pin "10") (pinfunction "GND_10") (pintype "power_in"))
      (node (ref "IC1") (pin "12") (pinfunction "CET_12") (pintype "input"))
      (node (ref "IC10") (pin "15") (pinfunction "G_15") (pintype "input"))
      (node (ref "IC10") (pin "8") (pinfunction "GND_8") (pintype "power_in"))
      (node (ref "IC11") (pin "15") (pinfunction "G_15") (pintype "input"))
      (node (ref "IC11") (pin "8") (pinfunction "GND_8") (pintype "power_in"))
      (node (ref "IC12") (pin "10") (pinfunction "GND_10") (pintype "power_in"))
      (node (ref "IC12") (pin "12") (pinfunction "CET_12") (pintype "input"))
      (node (ref "IC13") (pin "10") (pinfunction "GND_10") (pintype "power_in"))
      (node (ref "IC14") (pin "10") (pinfunction "GND_10") (pintype "power_in"))
      (node (ref "IC15") (pin "10") (pinfunction "GND_10") (pintype "power_in"))
      (node (ref "IC16") (pin "10") (pinfunction "GND_10") (pintype "power_in"))
      (node (ref "IC16") (pin "12") (pinfunction "CET_12") (pintype "input"))
      (node (ref "IC17") (pin "10") (pinfunction "GND_10") (pintype "power_in"))
      (node (ref "IC18") (pin "10") (pinfunction "GND_10") (pintype "power_in"))
      (node (ref "IC19") (pin "10") (pinfunction "GND_10") (pintype "power_in"))
      (node (ref "IC2") (pin "10") (pinfunction "GND_10") (pintype "power_in"))
      (node (ref "IC3") (pin "10") (pinfunction "GND_10") (pintype "power_in"))
      (node (ref "IC4") (pin "10") (pinfunction "GND_10") (pintype "power_in"))
      (node (ref "IC5") (pin "10") (pinfunction "GND_10") (pintype "power_in"))
      (node (ref "IC5") (pin "12") (pinfunction "CET_12") (pintype "input"))
      (node (ref "IC6") (pin "10") (pinfunction "GND_10") (pintype "power_in"))
      (node (ref "IC7") (pin "10") (pinfunction "GND_10") (pintype "power_in"))
      (node (ref "IC8") (pin "10") (pinfunction "GND_10") (pintype "power_in"))
      (node (ref "IC9") (pin "7") (pinfunction "GND_7") (pintype "power_in"))
    )
    (net (code "58") (name "LOAD_FLAGS0") (class "Default")
      (node (ref "JP9") (pin "24") (pinfunction "24_24") (pintype "passive"))
    )
    (net (code "59") (name "LOAD_FLAGS1") (class "Default")
      (node (ref "JP9") (pin "26") (pinfunction "26_26") (pintype "passive"))
    )
    (net (code "60") (name "MDRLDINHBT") (class "Default")
      (node (ref "JP9") (pin "43") (pinfunction "43_43") (pintype "passive"))
    )
    (net (code "61") (name "MEMSEG") (class "Default")
      (node (ref "JP10") (pin "14") (pinfunction "14_14") (pintype "passive"))
    )
    (net (code "62") (name "Net-(IC1A-LOAD)") (class "Default")
      (node (ref "IC1") (pin "11") (pinfunction "LOAD_11") (pintype "input"))
      (node (ref "IC2") (pin "11") (pinfunction "LOAD_11") (pintype "input"))
      (node (ref "IC9") (pin "3") (pinfunction "O_3") (pintype "output"))
    )
    (net (code "63") (name "Net-(IC1A-RCO)") (class "Default")
      (node (ref "IC1") (pin "19") (pinfunction "RCO_19") (pintype "output"))
      (node (ref "IC2") (pin "12") (pinfunction "CET_12") (pintype "input"))
    )
    (net (code "64") (name "Net-(IC2A-RCO)") (class "Default")
      (node (ref "IC2") (pin "19") (pinfunction "RCO_19") (pintype "output"))
      (node (ref "IC3") (pin "12") (pinfunction "CET_12") (pintype "input"))
    )
    (net (code "65") (name "Net-(IC3A-LOAD)") (class "Default")
      (node (ref "IC3") (pin "11") (pinfunction "LOAD_11") (pintype "input"))
      (node (ref "IC4") (pin "11") (pinfunction "LOAD_11") (pintype "input"))
      (node (ref "IC9") (pin "6") (pinfunction "O_6") (pintype "output"))
    )
    (net (code "66") (name "Net-(IC3A-RCO)") (class "Default")
      (node (ref "IC3") (pin "19") (pinfunction "RCO_19") (pintype "output"))
      (node (ref "IC4") (pin "12") (pinfunction "CET_12") (pintype "input"))
    )
    (net (code "67") (name "Net-(IC5A-RCO)") (class "Default")
      (node (ref "IC5") (pin "19") (pinfunction "RCO_19") (pintype "output"))
      (node (ref "IC6") (pin "12") (pinfunction "CET_12") (pintype "input"))
    )
    (net (code "68") (name "Net-(IC6A-RCO)") (class "Default")
      (node (ref "IC6") (pin "19") (pinfunction "RCO_19") (pintype "output"))
      (node (ref "IC7") (pin "12") (pinfunction "CET_12") (pintype "input"))
    )
    (net (code "69") (name "Net-(IC7A-RCO)") (class "Default")
      (node (ref "IC7") (pin "19") (pinfunction "RCO_19") (pintype "output"))
      (node (ref "IC8") (pin "12") (pinfunction "CET_12") (pintype "input"))
    )
    (net (code "70") (name "Net-(IC10A-1Y)") (class "Default")
      (node (ref "IC10") (pin "4") (pinfunction "1Y_4") (pintype "output"))
      (node (ref "IC12") (pin "7") (pinfunction "CEP_7") (pintype "input"))
      (node (ref "IC13") (pin "7") (pinfunction "CEP_7") (pintype "input"))
      (node (ref "IC14") (pin "7") (pinfunction "CEP_7") (pintype "input"))
      (node (ref "IC15") (pin "7") (pinfunction "CEP_7") (pintype "input"))
    )
    (net (code "71") (name "Net-(IC10A-2Y)") (class "Default")
      (node (ref "IC10") (pin "7") (pinfunction "2Y_7") (pintype "output"))
      (node (ref "IC12") (pin "11") (pinfunction "LOAD_11") (pintype "input"))
      (node (ref "IC13") (pin "11") (pinfunction "LOAD_11") (pintype "input"))
      (node (ref "IC14") (pin "11") (pinfunction "LOAD_11") (pintype "input"))
      (node (ref "IC15") (pin "11") (pinfunction "LOAD_11") (pintype "input"))
    )
    (net (code "72") (name "Net-(IC10A-3Y)") (class "Default")
      (node (ref "IC10") (pin "9") (pinfunction "3Y_9") (pintype "output"))
      (node (ref "IC12") (pin "1") (pinfunction "U/~{D}_1") (pintype "input"))
      (node (ref "IC13") (pin "1") (pinfunction "U/~{D}_1") (pintype "input"))
      (node (ref "IC14") (pin "1") (pinfunction "U/~{D}_1") (pintype "input"))
      (node (ref "IC15") (pin "1") (pinfunction "U/~{D}_1") (pintype "input"))
    )
    (net (code "73") (name "Net-(IC10A-4Y)") (class "Default")
      (node (ref "IC10") (pin "12") (pinfunction "4Y_12") (pintype "output"))
      (node (ref "IC12") (pin "17") (pinfunction "OE_17") (pintype "input"))
      (node (ref "IC13") (pin "17") (pinfunction "OE_17") (pintype "input"))
      (node (ref "IC14") (pin "17") (pinfunction "OE_17") (pintype "input"))
      (node (ref "IC15") (pin "17") (pinfunction "OE_17") (pintype "input"))
    )
    (net (code "74") (name "Net-(IC11A-1Y)") (class "Default")
      (node (ref "IC11") (pin "4") (pinfunction "1Y_4") (pintype "output"))
      (node (ref "IC16") (pin "7") (pinfunction "CEP_7") (pintype "input"))
      (node (ref "IC17") (pin "7") (pinfunction "CEP_7") (pintype "input"))
      (node (ref "IC18") (pin "7") (pinfunction "CEP_7") (pintype "input"))
      (node (ref "IC19") (pin "7") (pinfunction "CEP_7") (pintype "input"))
    )
    (net (code "75") (name "Net-(IC11A-2Y)") (class "Default")
      (node (ref "IC11") (pin "7") (pinfunction "2Y_7") (pintype "output"))
      (node (ref "IC16") (pin "11") (pinfunction "LOAD_11") (pintype "input"))
      (node (ref "IC17") (pin "11") (pinfunction "LOAD_11") (pintype "input"))
      (node (ref "IC18") (pin "11") (pinfunction "LOAD_11") (pintype "input"))
      (node (ref "IC19") (pin "11") (pinfunction "LOAD_11") (pintype "input"))
    )
    (net (code "76") (name "Net-(IC11A-3Y)") (class "Default")
      (node (ref "IC11") (pin "9") (pinfunction "3Y_9") (pintype "output"))
      (node (ref "IC16") (pin "1") (pinfunction "U/~{D}_1") (pintype "input"))
      (node (ref "IC17") (pin "1") (pinfunction "U/~{D}_1") (pintype "input"))
      (node (ref "IC18") (pin "1") (pinfunction "U/~{D}_1") (pintype "input"))
      (node (ref "IC19") (pin "1") (pinfunction "U/~{D}_1") (pintype "input"))
    )
    (net (code "77") (name "Net-(IC11A-4Y)") (class "Default")
      (node (ref "IC11") (pin "12") (pinfunction "4Y_12") (pintype "output"))
      (node (ref "IC16") (pin "17") (pinfunction "OE_17") (pintype "input"))
      (node (ref "IC17") (pin "17") (pinfunction "OE_17") (pintype "input"))
      (node (ref "IC18") (pin "17") (pinfunction "OE_17") (pintype "input"))
      (node (ref "IC19") (pin "17") (pinfunction "OE_17") (pintype "input"))
    )
    (net (code "78") (name "Net-(IC12A-RCO)") (class "Default")
      (node (ref "IC12") (pin "19") (pinfunction "RCO_19") (pintype "output"))
      (node (ref "IC13") (pin "12") (pinfunction "CET_12") (pintype "input"))
    )
    (net (code "79") (name "Net-(IC13A-RCO)") (class "Default")
      (node (ref "IC13") (pin "19") (pinfunction "RCO_19") (pintype "output"))
      (node (ref "IC14") (pin "12") (pinfunction "CET_12") (pintype "input"))
    )
    (net (code "80") (name "Net-(IC14A-RCO)") (class "Default")
      (node (ref "IC14") (pin "19") (pinfunction "RCO_19") (pintype "output"))
      (node (ref "IC15") (pin "12") (pinfunction "CET_12") (pintype "input"))
    )
    (net (code "81") (name "Net-(IC16A-RCO)") (class "Default")
      (node (ref "IC16") (pin "19") (pinfunction "RCO_19") (pintype "output"))
      (node (ref "IC17") (pin "12") (pinfunction "CET_12") (pintype "input"))
    )
    (net (code "82") (name "Net-(IC17A-RCO)") (class "Default")
      (node (ref "IC17") (pin "19") (pinfunction "RCO_19") (pintype "output"))
      (node (ref "IC18") (pin "12") (pinfunction "CET_12") (pintype "input"))
    )
    (net (code "83") (name "Net-(IC18A-RCO)") (class "Default")
      (node (ref "IC18") (pin "19") (pinfunction "RCO_19") (pintype "output"))
      (node (ref "IC19") (pin "12") (pinfunction "CET_12") (pintype "input"))
    )
    (net (code "84") (name "PROT") (class "Default")
      (node (ref "JP10") (pin "21") (pinfunction "21_21") (pintype "passive"))
    )
    (net (code "85") (name "RST") (class "Default")
      (node (ref "JP10") (pin "9") (pinfunction "9_9") (pintype "passive"))
    )
    (net (code "86") (name "SP_DIR") (class "Default")
      (node (ref "IC10") (pin "10") (pinfunction "3B_10") (pintype "input"))
      (node (ref "IC11") (pin "11") (pinfunction "3A_11") (pintype "input"))
      (node (ref "JP10") (pin "20") (pinfunction "20_20") (pintype "passive"))
    )
    (net (code "87") (name "unconnected-(IC1A-CCO-Pad18)") (class "Default")
      (node (ref "IC1") (pin "18") (pinfunction "CCO_18") (pintype "output"))
    )
    (net (code "88") (name "unconnected-(IC2A-CCO-Pad18)") (class "Default")
      (node (ref "IC2") (pin "18") (pinfunction "CCO_18") (pintype "output"))
    )
    (net (code "89") (name "unconnected-(IC3A-CCO-Pad18)") (class "Default")
      (node (ref "IC3") (pin "18") (pinfunction "CCO_18") (pintype "output"))
    )
    (net (code "90") (name "unconnected-(IC4A-CCO-Pad18)") (class "Default")
      (node (ref "IC4") (pin "18") (pinfunction "CCO_18") (pintype "output"))
    )
    (net (code "91") (name "unconnected-(IC4A-RCO-Pad19)") (class "Default")
      (node (ref "IC4") (pin "19") (pinfunction "RCO_19") (pintype "output"))
    )
    (net (code "92") (name "unconnected-(IC5A-CCO-Pad18)") (class "Default")
      (node (ref "IC5") (pin "18") (pinfunction "CCO_18") (pintype "output"))
    )
    (net (code "93") (name "unconnected-(IC6A-CCO-Pad18)") (class "Default")
      (node (ref "IC6") (pin "18") (pinfunction "CCO_18") (pintype "output"))
    )
    (net (code "94") (name "unconnected-(IC7A-CCO-Pad18)") (class "Default")
      (node (ref "IC7") (pin "18") (pinfunction "CCO_18") (pintype "output"))
    )
    (net (code "95") (name "unconnected-(IC8A-CCO-Pad18)") (class "Default")
      (node (ref "IC8") (pin "18") (pinfunction "CCO_18") (pintype "output"))
    )
    (net (code "96") (name "unconnected-(IC8A-RCO-Pad19)") (class "Default")
      (node (ref "IC8") (pin "19") (pinfunction "RCO_19") (pintype "output"))
    )
    (net (code "97") (name "unconnected-(IC9C-O-Pad8)") (class "Default")
      (node (ref "IC9") (pin "8") (pinfunction "O_8") (pintype "output"))
    )
    (net (code "98") (name "unconnected-(IC9D-O-Pad11)") (class "Default")
      (node (ref "IC9") (pin "11") (pinfunction "O_11") (pintype "output"))
    )
    (net (code "99") (name "unconnected-(IC12A-CCO-Pad18)") (class "Default")
      (node (ref "IC12") (pin "18") (pinfunction "CCO_18") (pintype "output"))
    )
    (net (code "100") (name "unconnected-(IC13A-CCO-Pad18)") (class "Default")
      (node (ref "IC13") (pin "18") (pinfunction "CCO_18") (pintype "output"))
    )
    (net (code "101") (name "unconnected-(IC14A-CCO-Pad18)") (class "Default")
      (node (ref "IC14") (pin "18") (pinfunction "CCO_18") (pintype "output"))
    )
    (net (code "102") (name "unconnected-(IC15A-CCO-Pad18)") (class "Default")
      (node (ref "IC15") (pin "18") (pinfunction "CCO_18") (pintype "output"))
    )
    (net (code "103") (name "unconnected-(IC15A-RCO-Pad19)") (class "Default")
      (node (ref "IC15") (pin "19") (pinfunction "RCO_19") (pintype "output"))
    )
    (net (code "104") (name "unconnected-(IC16A-CCO-Pad18)") (class "Default")
      (node (ref "IC16") (pin "18") (pinfunction "CCO_18") (pintype "output"))
    )
    (net (code "105") (name "unconnected-(IC17A-CCO-Pad18)") (class "Default")
      (node (ref "IC17") (pin "18") (pinfunction "CCO_18") (pintype "output"))
    )
    (net (code "106") (name "unconnected-(IC18A-CCO-Pad18)") (class "Default")
      (node (ref "IC18") (pin "18") (pinfunction "CCO_18") (pintype "output"))
    )
    (net (code "107") (name "unconnected-(IC19A-CCO-Pad18)") (class "Default")
      (node (ref "IC19") (pin "18") (pinfunction "CCO_18") (pintype "output"))
    )
    (net (code "108") (name "unconnected-(IC19A-RCO-Pad19)") (class "Default")
      (node (ref "IC19") (pin "19") (pinfunction "RCO_19") (pintype "output"))
    )
    (net (code "109") (name "unconnected-(JP9-Pad15)") (class "Default")
      (node (ref "JP9") (pin "15") (pinfunction "15_15") (pintype "passive"))
    )
    (net (code "110") (name "unconnected-(JP9-Pad28)") (class "Default")
      (node (ref "JP9") (pin "28") (pinfunction "28_28") (pintype "passive"))
    )
    (net (code "111") (name "unconnected-(JP9-Pad30)") (class "Default")
      (node (ref "JP9") (pin "30") (pinfunction "30_30") (pintype "passive"))
    )
    (net (code "112") (name "unconnected-(JP9-Pad37)") (class "Default")
      (node (ref "JP9") (pin "37") (pinfunction "37_37") (pintype "passive"))
    )
    (net (code "113") (name "{slash}ALUCARRYIN") (class "Default")
      (node (ref "JP9") (pin "2") (pinfunction "2_2") (pintype "passive"))
    )
    (net (code "114") (name "{slash}ALUHI2MEM") (class "Default")
      (node (ref "JP10") (pin "25") (pinfunction "25_25") (pintype "passive"))
    )
    (net (code "115") (name "{slash}ALULO2MEM") (class "Default")
      (node (ref "JP10") (pin "29") (pinfunction "29_29") (pintype "passive"))
    )
    (net (code "116") (name "{slash}ALUSHR") (class "Default")
      (node (ref "JP9") (pin "1") (pinfunction "1_1") (pintype "passive"))
    )
    (net (code "117") (name "{slash}BUSIFCEN") (class "Default")
      (node (ref "JP10") (pin "5") (pinfunction "5_5") (pintype "passive"))
    )
    (net (code "118") (name "{slash}CARRY1") (class "Default")
      (node (ref "JP9") (pin "29") (pinfunction "29_29") (pintype "passive"))
    )
    (net (code "119") (name "{slash}CARRY3") (class "Default")
      (node (ref "JP9") (pin "31") (pinfunction "31_31") (pintype "passive"))
    )
    (net (code "120") (name "{slash}CNTSP") (class "Default")
      (node (ref "IC10") (pin "3") (pinfunction "1B_3") (pintype "input"))
      (node (ref "IC11") (pin "2") (pinfunction "1A_2") (pintype "input"))
      (node (ref "JP10") (pin "3") (pinfunction "3_3") (pintype "passive"))
    )
    (net (code "121") (name "{slash}ENA") (class "Default")
      (node (ref "JP9") (pin "33") (pinfunction "33_33") (pintype "passive"))
    )
    (net (code "122") (name "{slash}ENABUS") (class "Default")
      (node (ref "JP10") (pin "22") (pinfunction "22_22") (pintype "passive"))
    )
    (net (code "123") (name "{slash}ENALU") (class "Default")
      (node (ref "JP9") (pin "39") (pinfunction "39_39") (pintype "passive"))
    )
    (net (code "124") (name "{slash}ENDP") (class "Default")
      (node (ref "JP9") (pin "44") (pinfunction "44_44") (pintype "passive"))
    )
    (net (code "125") (name "{slash}ENIPTR") (class "Default")
      (node (ref "JP9") (pin "38") (pinfunction "38_38") (pintype "passive"))
    )
    (net (code "126") (name "{slash}ENLMDR") (class "Default")
      (node (ref "JP9") (pin "34") (pinfunction "34_34") (pintype "passive"))
    )
    (net (code "127") (name "{slash}ENMAR") (class "Default")
      (node (ref "IC1") (pin "17") (pinfunction "OE_17") (pintype "input"))
      (node (ref "IC2") (pin "17") (pinfunction "OE_17") (pintype "input"))
      (node (ref "IC3") (pin "17") (pinfunction "OE_17") (pintype "input"))
      (node (ref "IC4") (pin "17") (pinfunction "OE_17") (pintype "input"))
      (node (ref "JP9") (pin "48") (pinfunction "48_48") (pintype "passive"))
    )
    (net (code "128") (name "{slash}ENMEM") (class "Default")
      (node (ref "JP10") (pin "16") (pinfunction "16_16") (pintype "passive"))
    )
    (net (code "129") (name "{slash}ENMSW") (class "Default")
      (node (ref "JP9") (pin "40") (pinfunction "40_40") (pintype "passive"))
    )
    (net (code "130") (name "{slash}ENPC") (class "Default")
      (node (ref "IC5") (pin "17") (pinfunction "OE_17") (pintype "input"))
      (node (ref "IC6") (pin "17") (pinfunction "OE_17") (pintype "input"))
      (node (ref "IC7") (pin "17") (pinfunction "OE_17") (pintype "input"))
      (node (ref "IC8") (pin "17") (pinfunction "OE_17") (pintype "input"))
      (node (ref "JP9") (pin "42") (pinfunction "42_42") (pintype "passive"))
    )
    (net (code "131") (name "{slash}ENRMDR") (class "Default")
      (node (ref "JP9") (pin "41") (pinfunction "41_41") (pintype "passive"))
    )
    (net (code "132") (name "{slash}ENSP") (class "Default")
      (node (ref "IC10") (pin "13") (pinfunction "4B_13") (pintype "input"))
      (node (ref "IC11") (pin "14") (pinfunction "4A_14") (pintype "input"))
      (node (ref "JP9") (pin "46") (pinfunction "46_46") (pintype "passive"))
    )
    (net (code "133") (name "{slash}ENX") (class "Default")
      (node (ref "JP9") (pin "36") (pinfunction "36_36") (pintype "passive"))
    )
    (net (code "134") (name "{slash}ENY") (class "Default")
      (node (ref "JP9") (pin "35") (pinfunction "35_35") (pintype "passive"))
    )
    (net (code "135") (name "{slash}FI") (class "Default")
      (node (ref "JP10") (pin "32") (pinfunction "32_32") (pintype "passive"))
    )
    (net (code "136") (name "{slash}FP") (class "Default")
      (node (ref "JP10") (pin "34") (pinfunction "34_34") (pintype "passive"))
    )
    (net (code "137") (name "{slash}FS") (class "Default")
      (node (ref "IC10") (pin "1") (pinfunction "~{A}/B_1") (pintype "input"))
      (node (ref "IC11") (pin "1") (pinfunction "~{A}/B_1") (pintype "input"))
      (node (ref "JP10") (pin "30") (pinfunction "30_30") (pintype "passive"))
    )
    (net (code "138") (name "{slash}INCPC") (class "Default")
      (node (ref "IC5") (pin "7") (pinfunction "CEP_7") (pintype "input"))
      (node (ref "IC6") (pin "7") (pinfunction "CEP_7") (pintype "input"))
      (node (ref "IC7") (pin "7") (pinfunction "CEP_7") (pintype "input"))
      (node (ref "IC8") (pin "7") (pinfunction "CEP_7") (pintype "input"))
      (node (ref "JP10") (pin "1") (pinfunction "1_1") (pintype "passive"))
    )
    (net (code "139") (name "{slash}INC_MAR") (class "Default")
      (node (ref "IC1") (pin "7") (pinfunction "CEP_7") (pintype "input"))
      (node (ref "IC2") (pin "7") (pinfunction "CEP_7") (pintype "input"))
      (node (ref "IC3") (pin "7") (pinfunction "CEP_7") (pintype "input"))
      (node (ref "IC4") (pin "7") (pinfunction "CEP_7") (pintype "input"))
      (node (ref "JP9") (pin "32") (pinfunction "32_32") (pintype "passive"))
    )
    (net (code "140") (name "{slash}IO") (class "Default")
      (node (ref "JP10") (pin "35") (pinfunction "35_35") (pintype "passive"))
    )
    (net (code "141") (name "{slash}LATCHFLAGS") (class "Default")
      (node (ref "JP10") (pin "12") (pinfunction "12_12") (pintype "passive"))
    )
    (net (code "142") (name "{slash}LATCH_I") (class "Default")
      (node (ref "JP9") (pin "47") (pinfunction "47_47") (pintype "passive"))
    )
    (net (code "143") (name "{slash}LATCH_S") (class "Default")
      (node (ref "JP9") (pin "45") (pinfunction "45_45") (pintype "passive"))
    )
    (net (code "144") (name "{slash}LDA") (class "Default")
      (node (ref "JP9") (pin "14") (pinfunction "14_14") (pintype "passive"))
    )
    (net (code "145") (name "{slash}LDAHI") (class "Default")
      (node (ref "JP9") (pin "11") (pinfunction "11_11") (pintype "passive"))
    )
    (net (code "146") (name "{slash}LDALO") (class "Default")
      (node (ref "JP9") (pin "12") (pinfunction "12_12") (pintype "passive"))
    )
    (net (code "147") (name "{slash}LDDP") (class "Default")
      (node (ref "JP9") (pin "22") (pinfunction "22_22") (pintype "passive"))
    )
    (net (code "148") (name "{slash}LDMAR") (class "Default")
      (node (ref "IC9") (pin "1") (pinfunction "I0_1") (pintype "input"))
      (node (ref "IC9") (pin "4") (pinfunction "I0_4") (pintype "input"))
      (node (ref "JP9") (pin "23") (pinfunction "23_23") (pintype "passive"))
    )
    (net (code "149") (name "{slash}LDMARHI") (class "Default")
      (node (ref "IC9") (pin "5") (pinfunction "I1_5") (pintype "input"))
      (node (ref "JP9") (pin "17") (pinfunction "17_17") (pintype "passive"))
    )
    (net (code "150") (name "{slash}LDMARLO") (class "Default")
      (node (ref "IC9") (pin "2") (pinfunction "I1_2") (pintype "input"))
      (node (ref "JP9") (pin "18") (pinfunction "18_18") (pintype "passive"))
    )
    (net (code "151") (name "{slash}LDMDR") (class "Default")
      (node (ref "JP9") (pin "9") (pinfunction "9_9") (pintype "passive"))
    )
    (net (code "152") (name "{slash}LDMDRHI") (class "Default")
      (node (ref "JP9") (pin "10") (pinfunction "10_10") (pintype "passive"))
    )
    (net (code "153") (name "{slash}LDMDRLO") (class "Default")
      (node (ref "JP9") (pin "7") (pinfunction "7_7") (pintype "passive"))
    )
    (net (code "154") (name "{slash}LDMEM") (class "Default")
      (node (ref "JP10") (pin "15") (pinfunction "15_15") (pintype "passive"))
    )
    (net (code "155") (name "{slash}LDMSW") (class "Default")
      (node (ref "JP9") (pin "20") (pinfunction "20_20") (pintype "passive"))
    )
    (net (code "156") (name "{slash}LDPC") (class "Default")
      (node (ref "IC5") (pin "11") (pinfunction "LOAD_11") (pintype "input"))
      (node (ref "IC6") (pin "11") (pinfunction "LOAD_11") (pintype "input"))
      (node (ref "IC7") (pin "11") (pinfunction "LOAD_11") (pintype "input"))
      (node (ref "IC8") (pin "11") (pinfunction "LOAD_11") (pintype "input"))
      (node (ref "JP9") (pin "19") (pinfunction "19_19") (pintype "passive"))
    )
    (net (code "157") (name "{slash}LDSP") (class "Default")
      (node (ref "IC10") (pin "6") (pinfunction "2B_6") (pintype "input"))
      (node (ref "IC11") (pin "5") (pinfunction "2A_5") (pintype "input"))
      (node (ref "JP9") (pin "21") (pinfunction "21_21") (pintype "passive"))
    )
    (net (code "158") (name "{slash}LDX") (class "Default")
      (node (ref "JP9") (pin "13") (pinfunction "13_13") (pintype "passive"))
    )
    (net (code "159") (name "{slash}LDY") (class "Default")
      (node (ref "JP9") (pin "16") (pinfunction "16_16") (pintype "passive"))
    )
    (net (code "160") (name "{slash}LOAD_IR") (class "Default")
      (node (ref "JP10") (pin "26") (pinfunction "26_26") (pintype "passive"))
    )
    (net (code "161") (name "{slash}MEM2ALUHI") (class "Default")
      (node (ref "JP10") (pin "27") (pinfunction "27_27") (pintype "passive"))
    )
    (net (code "162") (name "{slash}MEM2ALULO") (class "Default")
      (node (ref "JP10") (pin "31") (pinfunction "31_31") (pintype "passive"))
    )
    (net (code "163") (name "{slash}MEMOP") (class "Default")
      (node (ref "JP10") (pin "11") (pinfunction "11_11") (pintype "passive"))
    )
    (net (code "164") (name "{slash}NP_FAULT") (class "Default")
      (node (ref "JP10") (pin "36") (pinfunction "36_36") (pintype "passive"))
    )
    (net (code "165") (name "{slash}RST") (class "Default")
      (node (ref "IC5") (pin "9") (pinfunction "SCLR_9") (pintype "input"))
      (node (ref "IC6") (pin "9") (pinfunction "SCLR_9") (pintype "input"))
      (node (ref "IC7") (pin "9") (pinfunction "SCLR_9") (pintype "input"))
      (node (ref "IC8") (pin "9") (pinfunction "SCLR_9") (pintype "input"))
      (node (ref "JP10") (pin "7") (pinfunction "7_7") (pintype "passive"))
    )
    (net (code "166") (name "{slash}WR_FAULT") (class "Default")
      (node (ref "JP10") (pin "33") (pinfunction "33_33") (pintype "passive"))
    )
  )
)
